# WATCH_LOW_TECH.net
KiCad netlist of a schematic drawn in EAGLE
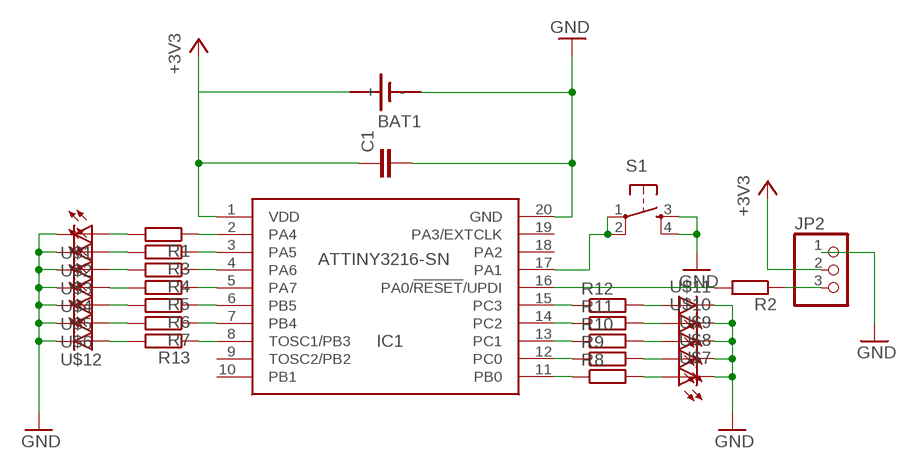
[diagram p0: schematic, sheet 1]

(export (version "E")
  (design (tool "Eeschema 10.0.6"))
  (components
    (comp (ref "BAT1")
      (value "SN2032")
      (footprint "eagle-import:SN2032")
      (libsource (lib "eagle-import") (part "SN2032"))
    )
    (comp (ref "C1")
      (value "C-EUC1206")
      (footprint "eagle-import:C1206")
      (libsource (lib "eagle-import") (part "C-EUC1206"))
    )
    (comp (ref "IC1")
      (value "ATTINY3216-SN")
      (footprint "eagle-import:SOIC127P1030X265-20N")
      (fields (field (name "MF") "Microchip Technology"))
      (libsource (lib "eagle-import") (part "ATTINY3216-SN"))
    )
    (comp (ref "JP2")
      (value "PINHD-1X03_2.54")
      (footprint "eagle-import:1X03")
      (libsource (lib "eagle-import") (part "PINHD-1X03_2.54"))
    )
    (comp (ref "R1")
      (value "R-EU_R1206")
      (footprint "eagle-import:R1206")
      (libsource (lib "eagle-import") (part "R-EU_R1206"))
    )
    (comp (ref "R2")
      (value "R-EU_R1206")
      (footprint "eagle-import:R1206")
      (libsource (lib "eagle-import") (part "R-EU_R1206"))
    )
    (comp (ref "R3")
      (value "R-EU_R1206")
      (footprint "eagle-import:R1206")
      (libsource (lib "eagle-import") (part "R-EU_R1206"))
    )
    (comp (ref "R4")
      (value "R-EU_R1206")
      (footprint "eagle-import:R1206")
      (libsource (lib "eagle-import") (part "R-EU_R1206"))
    )
    (comp (ref "R5")
      (value "R-EU_R1206")
      (footprint "eagle-import:R1206")
      (libsource (lib "eagle-import") (part "R-EU_R1206"))
    )
    (comp (ref "R6")
      (value "R-EU_R1206")
      (footprint "eagle-import:R1206")
      (libsource (lib "eagle-import") (part "R-EU_R1206"))
    )
    (comp (ref "R7")
      (value "R-EU_R1206")
      (footprint "eagle-import:R1206")
      (libsource (lib "eagle-import") (part "R-EU_R1206"))
    )
    (comp (ref "R8")
      (value "R-EU_R1206")
      (footprint "eagle-import:R1206")
      (libsource (lib "eagle-import") (part "R-EU_R1206"))
    )
    (comp (ref "R9")
      (value "R-EU_R1206")
      (footprint "eagle-import:R1206")
      (libsource (lib "eagle-import") (part "R-EU_R1206"))
    )
    (comp (ref "R10")
      (value "R-EU_R1206")
      (footprint "eagle-import:R1206")
      (libsource (lib "eagle-import") (part "R-EU_R1206"))
    )
    (comp (ref "R11")
      (value "R-EU_R1206")
      (footprint "eagle-import:R1206")
      (libsource (lib "eagle-import") (part "R-EU_R1206"))
    )
    (comp (ref "R12")
      (value "R-EU_R1206")
      (footprint "eagle-import:R1206")
      (libsource (lib "eagle-import") (part "R-EU_R1206"))
    )
    (comp (ref "R13")
      (value "R-EU_R1206")
      (footprint "eagle-import:R1206")
      (libsource (lib "eagle-import") (part "R-EU_R1206"))
    )
    (comp (ref "S1")
      (value "6MM_SWITCH6MM_SWITCH")
      (footprint "eagle-import:6MM_SWITCH")
      (libsource (lib "eagle-import") (part "6MM_SWITCH6MM_SWITCH"))
    )
    (comp (ref "U$1")
      (value "LEDFAB1206")
      (footprint "eagle-import:LED1206FAB")
      (libsource (lib "eagle-import") (part "LEDFAB1206"))
    )
    (comp (ref "U$2")
      (value "LEDFAB1206")
      (footprint "eagle-import:LED1206FAB")
      (libsource (lib "eagle-import") (part "LEDFAB1206"))
    )
    (comp (ref "U$3")
      (value "LEDFAB1206")
      (footprint "eagle-import:LED1206FAB")
      (libsource (lib "eagle-import") (part "LEDFAB1206"))
    )
    (comp (ref "U$4")
      (value "LEDFAB1206")
      (footprint "eagle-import:LED1206FAB")
      (libsource (lib "eagle-import") (part "LEDFAB1206"))
    )
    (comp (ref "U$5")
      (value "LEDFAB1206")
      (footprint "eagle-import:LED1206FAB")
      (libsource (lib "eagle-import") (part "LEDFAB1206"))
    )
    (comp (ref "U$6")
      (value "LEDFAB1206")
      (footprint "eagle-import:LED1206FAB")
      (libsource (lib "eagle-import") (part "LEDFAB1206"))
    )
    (comp (ref "U$7")
      (value "LEDFAB1206")
      (footprint "eagle-import:LED1206FAB")
      (libsource (lib "eagle-import") (part "LEDFAB1206"))
    )
    (comp (ref "U$8")
      (value "LEDFAB1206")
      (footprint "eagle-import:LED1206FAB")
      (libsource (lib "eagle-import") (part "LEDFAB1206"))
    )
    (comp (ref "U$9")
      (value "LEDFAB1206")
      (footprint "eagle-import:LED1206FAB")
      (libsource (lib "eagle-import") (part "LEDFAB1206"))
    )
    (comp (ref "U$10")
      (value "LEDFAB1206")
      (footprint "eagle-import:LED1206FAB")
      (libsource (lib "eagle-import") (part "LEDFAB1206"))
    )
    (comp (ref "U$11")
      (value "LEDFAB1206")
      (footprint "eagle-import:LED1206FAB")
      (libsource (lib "eagle-import") (part "LEDFAB1206"))
    )
    (comp (ref "U$12")
      (value "LEDFAB1206")
      (footprint "eagle-import:LED1206FAB")
      (libsource (lib "eagle-import") (part "LEDFAB1206"))
    )
  )
  (nets
    (net (code "1") (name "+3V3") (class "Default")
      (node (ref "BAT1") (pin "+") (pinfunction "+_+") (pintype "passive"))
      (node (ref "C1") (pin "1") (pinfunction "1_1") (pintype "passive"))
      (node (ref "IC1") (pin "1") (pinfunction "VDD_1") (pintype "bidirectional"))
      (node (ref "JP2") (pin "2") (pinfunction "2_2") (pintype "passive"))
    )
    (net (code "2") (name "GND") (class "Default")
      (node (ref "BAT1") (pin "-") (pinfunction "-_-") (pintype "passive"))
      (node (ref "C1") (pin "2") (pinfunction "2_2") (pintype "passive"))
      (node (ref "IC1") (pin "20") (pinfunction "GND_20") (pintype "bidirectional"))
      (node (ref "JP2") (pin "1") (pinfunction "1_1") (pintype "passive"))
      (node (ref "S1") (pin "3") (pinfunction "S_3") (pintype "passive"))
      (node (ref "S1") (pin "4") (pinfunction "S1_4") (pintype "passive"))
      (node (ref "U$1") (pin "2") (pinfunction "C_2") (pintype "passive"))
      (node (ref "U$10") (pin "2") (pinfunction "C_2") (pintype "passive"))
      (node (ref "U$11") (pin "2") (pinfunction "C_2") (pintype "passive"))
      (node (ref "U$12") (pin "2") (pinfunction "C_2") (pintype "passive"))
      (node (ref "U$2") (pin "2") (pinfunction "C_2") (pintype "passive"))
      (node (ref "U$3") (pin "2") (pinfunction "C_2") (pintype "passive"))
      (node (ref "U$4") (pin "2") (pinfunction "C_2") (pintype "passive"))
      (node (ref "U$5") (pin "2") (pinfunction "C_2") (pintype "passive"))
      (node (ref "U$6") (pin "2") (pinfunction "C_2") (pintype "passive"))
      (node (ref "U$7") (pin "2") (pinfunction "C_2") (pintype "passive"))
      (node (ref "U$8") (pin "2") (pinfunction "C_2") (pintype "passive"))
      (node (ref "U$9") (pin "2") (pinfunction "C_2") (pintype "passive"))
    )
    (net (code "3") (name "Net-(IC1-PA0{slash}~{RESET}{slash}UPDI)") (class "Default")
      (node (ref "IC1") (pin "16") (pinfunction "PA0/~{RESET}/UPDI_16") (pintype "bidirectional"))
      (node (ref "R2") (pin "2") (pinfunction "2_2") (pintype "passive"))
    )
    (net (code "4") (name "Net-(IC1-PA1)") (class "Default")
      (node (ref "IC1") (pin "17") (pinfunction "PA1_17") (pintype "bidirectional"))
      (node (ref "S1") (pin "1") (pinfunction "P_1") (pintype "passive"))
      (node (ref "S1") (pin "2") (pinfunction "P1_2") (pintype "passive"))
    )
    (net (code "5") (name "Net-(IC1-PA4)") (class "Default")
      (node (ref "IC1") (pin "2") (pinfunction "PA4_2") (pintype "bidirectional"))
      (node (ref "R1") (pin "1") (pinfunction "1_1") (pintype "passive"))
    )
    (net (code "6") (name "Net-(IC1-PA5)") (class "Default")
      (node (ref "IC1") (pin "3") (pinfunction "PA5_3") (pintype "bidirectional"))
      (node (ref "R3") (pin "1") (pinfunction "1_1") (pintype "passive"))
    )
    (net (code "7") (name "Net-(IC1-PA6)") (class "Default")
      (node (ref "IC1") (pin "4") (pinfunction "PA6_4") (pintype "bidirectional"))
      (node (ref "R4") (pin "1") (pinfunction "1_1") (pintype "passive"))
    )
    (net (code "8") (name "Net-(IC1-PA7)") (class "Default")
      (node (ref "IC1") (pin "5") (pinfunction "PA7_5") (pintype "bidirectional"))
      (node (ref "R5") (pin "1") (pinfunction "1_1") (pintype "passive"))
    )
    (net (code "9") (name "Net-(IC1-PB0)") (class "Default")
      (node (ref "IC1") (pin "11") (pinfunction "PB0_11") (pintype "bidirectional"))
      (node (ref "R8") (pin "1") (pinfunction "1_1") (pintype "passive"))
    )
    (net (code "10") (name "Net-(IC1-PB4)") (class "Default")
      (node (ref "IC1") (pin "7") (pinfunction "PB4_7") (pintype "bidirectional"))
      (node (ref "R7") (pin "1") (pinfunction "1_1") (pintype "passive"))
    )
    (net (code "11") (name "Net-(IC1-PB5)") (class "Default")
      (node (ref "IC1") (pin "6") (pinfunction "PB5_6") (pintype "bidirectional"))
      (node (ref "R6") (pin "1") (pinfunction "1_1") (pintype "passive"))
    )
    (net (code "12") (name "Net-(IC1-PC0)") (class "Default")
      (node (ref "IC1") (pin "12") (pinfunction "PC0_12") (pintype "bidirectional"))
      (node (ref "R9") (pin "1") (pinfunction "1_1") (pintype "passive"))
    )
    (net (code "13") (name "Net-(IC1-PC1)") (class "Default")
      (node (ref "IC1") (pin "13") (pinfunction "PC1_13") (pintype "bidirectional"))
      (node (ref "R10") (pin "1") (pinfunction "1_1") (pintype "passive"))
    )
    (net (code "14") (name "Net-(IC1-PC2)") (class "Default")
      (node (ref "IC1") (pin "14") (pinfunction "PC2_14") (pintype "bidirectional"))
      (node (ref "R11") (pin "1") (pinfunction "1_1") (pintype "passive"))
    )
    (net (code "15") (name "Net-(IC1-PC3)") (class "Default")
      (node (ref "IC1") (pin "15") (pinfunction "PC3_15") (pintype "bidirectional"))
      (node (ref "R12") (pin "1") (pinfunction "1_1") (pintype "passive"))
    )
    (net (code "16") (name "Net-(IC1-TOSC1{slash}PB3)") (class "Default")
      (node (ref "IC1") (pin "8") (pinfunction "TOSC1/PB3_8") (pintype "bidirectional"))
      (node (ref "R13") (pin "1") (pinfunction "1_1") (pintype "passive"))
    )
    (net (code "17") (name "Net-(JP2-Pad3)") (class "Default")
      (node (ref "JP2") (pin "3") (pinfunction "3_3") (pintype "passive"))
      (node (ref "R2") (pin "1") (pinfunction "1_1") (pintype "passive"))
    )
    (net (code "18") (name "Net-(U$1-A)") (class "Default")
      (node (ref "R1") (pin "2") (pinfunction "2_2") (pintype "passive"))
      (node (ref "U$1") (pin "1") (pinfunction "A_1") (pintype "passive"))
    )
    (net (code "19") (name "Net-(U$2-A)") (class "Default")
      (node (ref "R3") (pin "2") (pinfunction "2_2") (pintype "passive"))
      (node (ref "U$2") (pin "1") (pinfunction "A_1") (pintype "passive"))
    )
    (net (code "20") (name "Net-(U$3-A)") (class "Default")
      (node (ref "R4") (pin "2") (pinfunction "2_2") (pintype "passive"))
      (node (ref "U$3") (pin "1") (pinfunction "A_1") (pintype "passive"))
    )
    (net (code "21") (name "Net-(U$4-A)") (class "Default")
      (node (ref "R5") (pin "2") (pinfunction "2_2") (pintype "passive"))
      (node (ref "U$4") (pin "1") (pinfunction "A_1") (pintype "passive"))
    )
    (net (code "22") (name "Net-(U$5-A)") (class "Default")
      (node (ref "R6") (pin "2") (pinfunction "2_2") (pintype "passive"))
      (node (ref "U$5") (pin "1") (pinfunction "A_1") (pintype "passive"))
    )
    (net (code "23") (name "Net-(U$6-A)") (class "Default")
      (node (ref "R7") (pin "2") (pinfunction "2_2") (pintype "passive"))
      (node (ref "U$6") (pin "1") (pinfunction "A_1") (pintype "passive"))
    )
    (net (code "24") (name "Net-(U$7-A)") (class "Default")
      (node (ref "R8") (pin "2") (pinfunction "2_2") (pintype "passive"))
      (node (ref "U$7") (pin "1") (pinfunction "A_1") (pintype "passive"))
    )
    (net (code "25") (name "Net-(U$8-A)") (class "Default")
      (node (ref "R9") (pin "2") (pinfunction "2_2") (pintype "passive"))
      (node (ref "U$8") (pin "1") (pinfunction "A_1") (pintype "passive"))
    )
    (net (code "26") (name "Net-(U$9-A)") (class "Default")
      (node (ref "R10") (pin "2") (pinfunction "2_2") (pintype "passive"))
      (node (ref "U$9") (pin "1") (pinfunction "A_1") (pintype "passive"))
    )
    (net (code "27") (name "Net-(U$10-A)") (class "Default")
      (node (ref "R11") (pin "2") (pinfunction "2_2") (pintype "passive"))
      (node (ref "U$10") (pin "1") (pinfunction "A_1") (pintype "passive"))
    )
    (net (code "28") (name "Net-(U$11-A)") (class "Default")
      (node (ref "R12") (pin "2") (pinfunction "2_2") (pintype "passive"))
      (node (ref "U$11") (pin "1") (pinfunction "A_1") (pintype "passive"))
    )
    (net (code "29") (name "Net-(U$12-A)") (class "Default")
      (node (ref "R13") (pin "2") (pinfunction "2_2") (pintype "passive"))
      (node (ref "U$12") (pin "1") (pinfunction "A_1") (pintype "passive"))
    )
    (net (code "30") (name "unconnected-(IC1-PA2-Pad18)") (class "Default")
      (node (ref "IC1") (pin "18") (pinfunction "PA2_18") (pintype "bidirectional"))
    )
    (net (code "31") (name "unconnected-(IC1-PA3{slash}EXTCLK-Pad19)") (class "Default")
      (node (ref "IC1") (pin "19") (pinfunction "PA3/EXTCLK_19") (pintype "bidirectional"))
    )
    (net (code "32") (name "unconnected-(IC1-PB1-Pad10)") (class "Default")
      (node (ref "IC1") (pin "10") (pinfunction "PB1_10") (pintype "bidirectional"))
    )
    (net (code "33") (name "unconnected-(IC1-TOSC2{slash}PB2-Pad9)") (class "Default")
      (node (ref "IC1") (pin "9") (pinfunction "TOSC2/PB2_9") (pintype "bidirectional"))
    )
  )
)
